# FDL-3_CTRL_-_v1_4.net
KiCad netlist of a schematic drawn in EAGLE
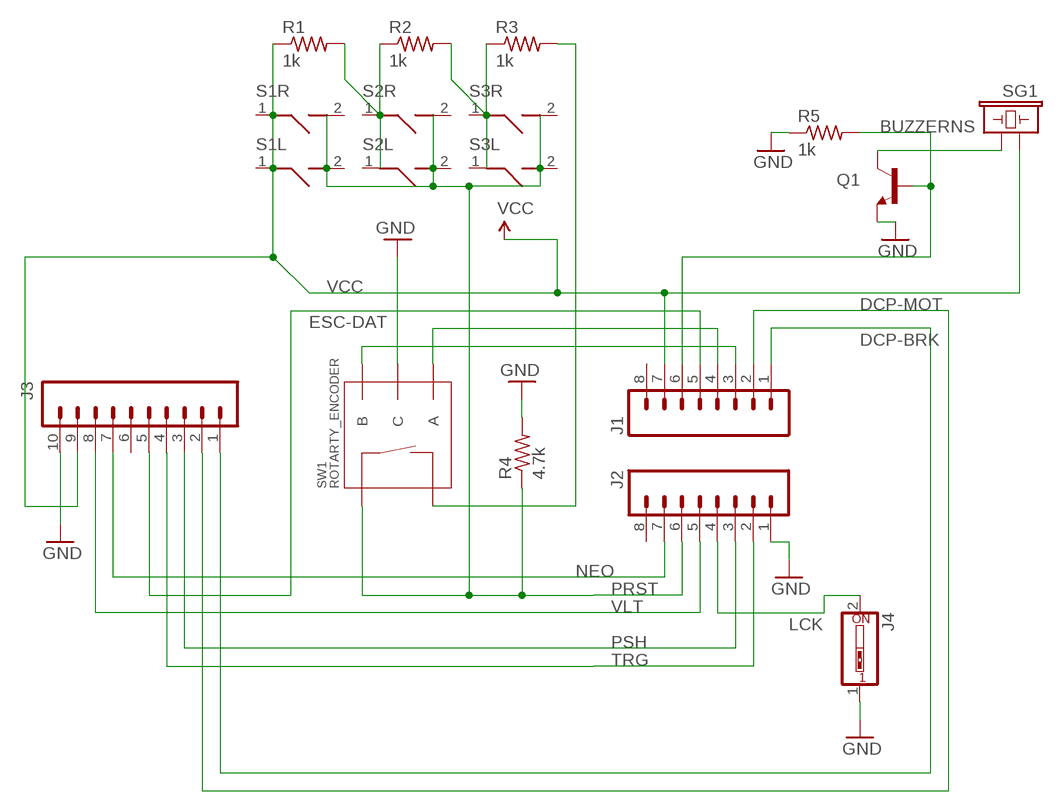
[diagram p0: schematic, sheet 1]

(export (version "E")
  (design (tool "Eeschema 10.0.6"))
  (components
    (comp (ref "J1")
      (value "M08SILK_FEMALE_PTH")
      (footprint "eagle-import:1X08")
      (libsource (lib "eagle-import") (part "M08SILK_FEMALE_PTH"))
    )
    (comp (ref "J2")
      (value "M08SILK_FEMALE_PTH")
      (footprint "eagle-import:1X08")
      (libsource (lib "eagle-import") (part "M08SILK_FEMALE_PTH"))
    )
    (comp (ref "J3")
      (value "M10SILK_FEMALE_PTH")
      (footprint "eagle-import:1X10")
      (libsource (lib "eagle-import") (part "M10SILK_FEMALE_PTH"))
    )
    (comp (ref "J4")
      (value "SW_DIP-1")
      (footprint "eagle-import:EDG-01")
      (libsource (lib "eagle-import") (part "SW_DIP-1"))
    )
    (comp (ref "Q1")
      (value "TRANSISTOR_NPNBC547")
      (footprint "eagle-import:TO-92-AMMO")
      (libsource (lib "eagle-import") (part "TRANSISTOR_NPNBC547"))
    )
    (comp (ref "R1")
      (value "1k")
      (footprint "eagle-import:0204_5")
      (libsource (lib "eagle-import") (part "R-US_0204/5"))
    )
    (comp (ref "R2")
      (value "1k")
      (footprint "eagle-import:0204_5")
      (libsource (lib "eagle-import") (part "R-US_0204/5"))
    )
    (comp (ref "R3")
      (value "1k")
      (footprint "eagle-import:0204_5")
      (libsource (lib "eagle-import") (part "R-US_0204/5"))
    )
    (comp (ref "R4")
      (value "4.7k")
      (footprint "eagle-import:0204_5")
      (libsource (lib "eagle-import") (part "R-US_0204/5"))
    )
    (comp (ref "R5")
      (value "1k")
      (footprint "eagle-import:0204_5")
      (libsource (lib "eagle-import") (part "R-US_0204/5"))
    )
    (comp (ref "S1L")
      (value "RGTANGTCTBTN")
      (footprint "eagle-import:RGTANGTCTBTN")
      (libsource (lib "eagle-import") (part "RGTANGTCTBTN"))
    )
    (comp (ref "S1R")
      (value "RGTANGTCTBTN")
      (footprint "eagle-import:RGTANGTCTBTN")
      (libsource (lib "eagle-import") (part "RGTANGTCTBTN"))
    )
    (comp (ref "S2L")
      (value "RGTANGTCTBTN")
      (footprint "eagle-import:RGTANGTCTBTN")
      (libsource (lib "eagle-import") (part "RGTANGTCTBTN"))
    )
    (comp (ref "S2R")
      (value "RGTANGTCTBTN")
      (footprint "eagle-import:RGTANGTCTBTN")
      (libsource (lib "eagle-import") (part "RGTANGTCTBTN"))
    )
    (comp (ref "S3L")
      (value "RGTANGTCTBTN")
      (footprint "eagle-import:RGTANGTCTBTN")
      (libsource (lib "eagle-import") (part "RGTANGTCTBTN"))
    )
    (comp (ref "S3R")
      (value "RGTANGTCTBTN")
      (footprint "eagle-import:RGTANGTCTBTN")
      (libsource (lib "eagle-import") (part "RGTANGTCTBTN"))
    )
    (comp (ref "SG1")
      (value "BUZZERNS")
      (footprint "eagle-import:BUZZER-12MM-NS")
      (libsource (lib "eagle-import") (part "BUZZERNS"))
    )
    (comp (ref "SW1")
      (value "ROTARTY_ENCODER")
      (footprint "eagle-import:ROTARY_ENC_PLAIN")
      (libsource (lib "eagle-import") (part "ROTARTY_ENCODER"))
    )
  )
  (nets
    (net (code "1") (name "/DCP-BRK") (class "Default")
      (node (ref "J1") (pin "1") (pinfunction "1_1") (pintype "passive"))
      (node (ref "J3") (pin "1") (pinfunction "1_1") (pintype "passive"))
    )
    (net (code "2") (name "/DCP-MOT") (class "Default")
      (node (ref "J1") (pin "2") (pinfunction "2_2") (pintype "passive"))
      (node (ref "J3") (pin "2") (pinfunction "2_2") (pintype "passive"))
    )
    (net (code "3") (name "/ESC-DAT") (class "Default")
      (node (ref "J1") (pin "5") (pinfunction "5_5") (pintype "passive"))
      (node (ref "J3") (pin "5") (pinfunction "5_5") (pintype "passive"))
    )
    (net (code "4") (name "/LCK") (class "Default")
      (node (ref "J2") (pin "4") (pinfunction "4_4") (pintype "passive"))
      (node (ref "J4") (pin "2") (pinfunction "2_2") (pintype "passive"))
    )
    (net (code "5") (name "/NEO") (class "Default")
      (node (ref "J2") (pin "7") (pinfunction "7_7") (pintype "passive"))
      (node (ref "J3") (pin "7") (pinfunction "7_7") (pintype "passive"))
    )
    (net (code "6") (name "/PRST") (class "Default")
      (node (ref "J2") (pin "6") (pinfunction "6_6") (pintype "passive"))
      (node (ref "R4") (pin "1") (pinfunction "1_1") (pintype "passive"))
      (node (ref "S1L") (pin "2") (pinfunction "2_2") (pintype "bidirectional"))
      (node (ref "S1R") (pin "2") (pinfunction "2_2") (pintype "bidirectional"))
      (node (ref "S2L") (pin "2") (pinfunction "2_2") (pintype "bidirectional"))
      (node (ref "S2R") (pin "2") (pinfunction "2_2") (pintype "bidirectional"))
      (node (ref "S3L") (pin "2") (pinfunction "2_2") (pintype "bidirectional"))
      (node (ref "S3R") (pin "2") (pinfunction "2_2") (pintype "bidirectional"))
      (node (ref "SW1") (pin "SW+") (pinfunction "SW+_SW+") (pintype "bidirectional"))
    )
    (net (code "7") (name "/PSH") (class "Default")
      (node (ref "J2") (pin "3") (pinfunction "3_3") (pintype "passive"))
      (node (ref "J3") (pin "3") (pinfunction "3_3") (pintype "passive"))
    )
    (net (code "8") (name "/TRG") (class "Default")
      (node (ref "J2") (pin "2") (pinfunction "2_2") (pintype "passive"))
      (node (ref "J3") (pin "4") (pinfunction "4_4") (pintype "passive"))
    )
    (net (code "9") (name "/VLT") (class "Default")
      (node (ref "J2") (pin "5") (pinfunction "5_5") (pintype "passive"))
      (node (ref "J3") (pin "8") (pinfunction "8_8") (pintype "passive"))
    )
    (net (code "10") (name "GND") (class "Default")
      (node (ref "J2") (pin "1") (pinfunction "1_1") (pintype "passive"))
      (node (ref "J3") (pin "10") (pinfunction "10_10") (pintype "passive"))
      (node (ref "J4") (pin "1") (pinfunction "1_1") (pintype "passive"))
      (node (ref "Q1") (pin "3") (pinfunction "E_3") (pintype "passive"))
      (node (ref "R4") (pin "2") (pinfunction "2_2") (pintype "passive"))
      (node (ref "R5") (pin "1") (pinfunction "1_1") (pintype "passive"))
      (node (ref "SW1") (pin "C") (pinfunction "C_C") (pintype "bidirectional"))
    )
    (net (code "11") (name "Net-(J1-Pad3)") (class "Default")
      (node (ref "J1") (pin "3") (pinfunction "3_3") (pintype "passive"))
      (node (ref "SW1") (pin "B") (pinfunction "B_B") (pintype "bidirectional"))
    )
    (net (code "12") (name "Net-(J1-Pad4)") (class "Default")
      (node (ref "J1") (pin "4") (pinfunction "4_4") (pintype "passive"))
      (node (ref "SW1") (pin "A") (pinfunction "A_A") (pintype "bidirectional"))
    )
    (net (code "13") (name "Net-(Q1-B)") (class "Default")
      (node (ref "J1") (pin "6") (pinfunction "6_6") (pintype "passive"))
      (node (ref "Q1") (pin "2") (pinfunction "B_2") (pintype "passive"))
      (node (ref "R5") (pin "2") (pinfunction "2_2") (pintype "passive"))
    )
    (net (code "14") (name "Net-(Q1-C)") (class "Default")
      (node (ref "Q1") (pin "1") (pinfunction "C_1") (pintype "passive"))
      (node (ref "SG1") (pin "-") (pinfunction "2_-") (pintype "passive"))
    )
    (net (code "15") (name "Net-(R1-Pad2)") (class "Default")
      (node (ref "R1") (pin "2") (pinfunction "2_2") (pintype "passive"))
      (node (ref "R2") (pin "1") (pinfunction "1_1") (pintype "passive"))
      (node (ref "S2L") (pin "1") (pinfunction "1_1") (pintype "bidirectional"))
      (node (ref "S2R") (pin "1") (pinfunction "1_1") (pintype "bidirectional"))
    )
    (net (code "16") (name "Net-(R2-Pad2)") (class "Default")
      (node (ref "R2") (pin "2") (pinfunction "2_2") (pintype "passive"))
      (node (ref "R3") (pin "1") (pinfunction "1_1") (pintype "passive"))
      (node (ref "S3L") (pin "1") (pinfunction "1_1") (pintype "bidirectional"))
      (node (ref "S3R") (pin "1") (pinfunction "1_1") (pintype "bidirectional"))
    )
    (net (code "17") (name "Net-(R3-Pad2)") (class "Default")
      (node (ref "R3") (pin "2") (pinfunction "2_2") (pintype "passive"))
      (node (ref "SW1") (pin "SW-") (pinfunction "SW-_SW-") (pintype "bidirectional"))
    )
    (net (code "18") (name "VCC") (class "Default")
      (node (ref "J1") (pin "7") (pinfunction "7_7") (pintype "passive"))
      (node (ref "J3") (pin "9") (pinfunction "9_9") (pintype "passive"))
      (node (ref "R1") (pin "1") (pinfunction "1_1") (pintype "passive"))
      (node (ref "S1L") (pin "1") (pinfunction "1_1") (pintype "bidirectional"))
      (node (ref "S1R") (pin "1") (pinfunction "1_1") (pintype "bidirectional"))
      (node (ref "SG1") (pin "+") (pinfunction "1_+") (pintype "passive"))
    )
    (net (code "19") (name "unconnected-(J1-Pad8)") (class "Default")
      (node (ref "J1") (pin "8") (pinfunction "8_8") (pintype "passive"))
    )
    (net (code "20") (name "unconnected-(J2-Pad8)") (class "Default")
      (node (ref "J2") (pin "8") (pinfunction "8_8") (pintype "passive"))
    )
    (net (code "21") (name "unconnected-(J3-Pad6)") (class "Default")
      (node (ref "J3") (pin "6") (pinfunction "6_6") (pintype "passive"))
    )
  )
)
